# CONTROLLER-RK3562.net
KiCad netlist of a schematic drawn in Altium Designer
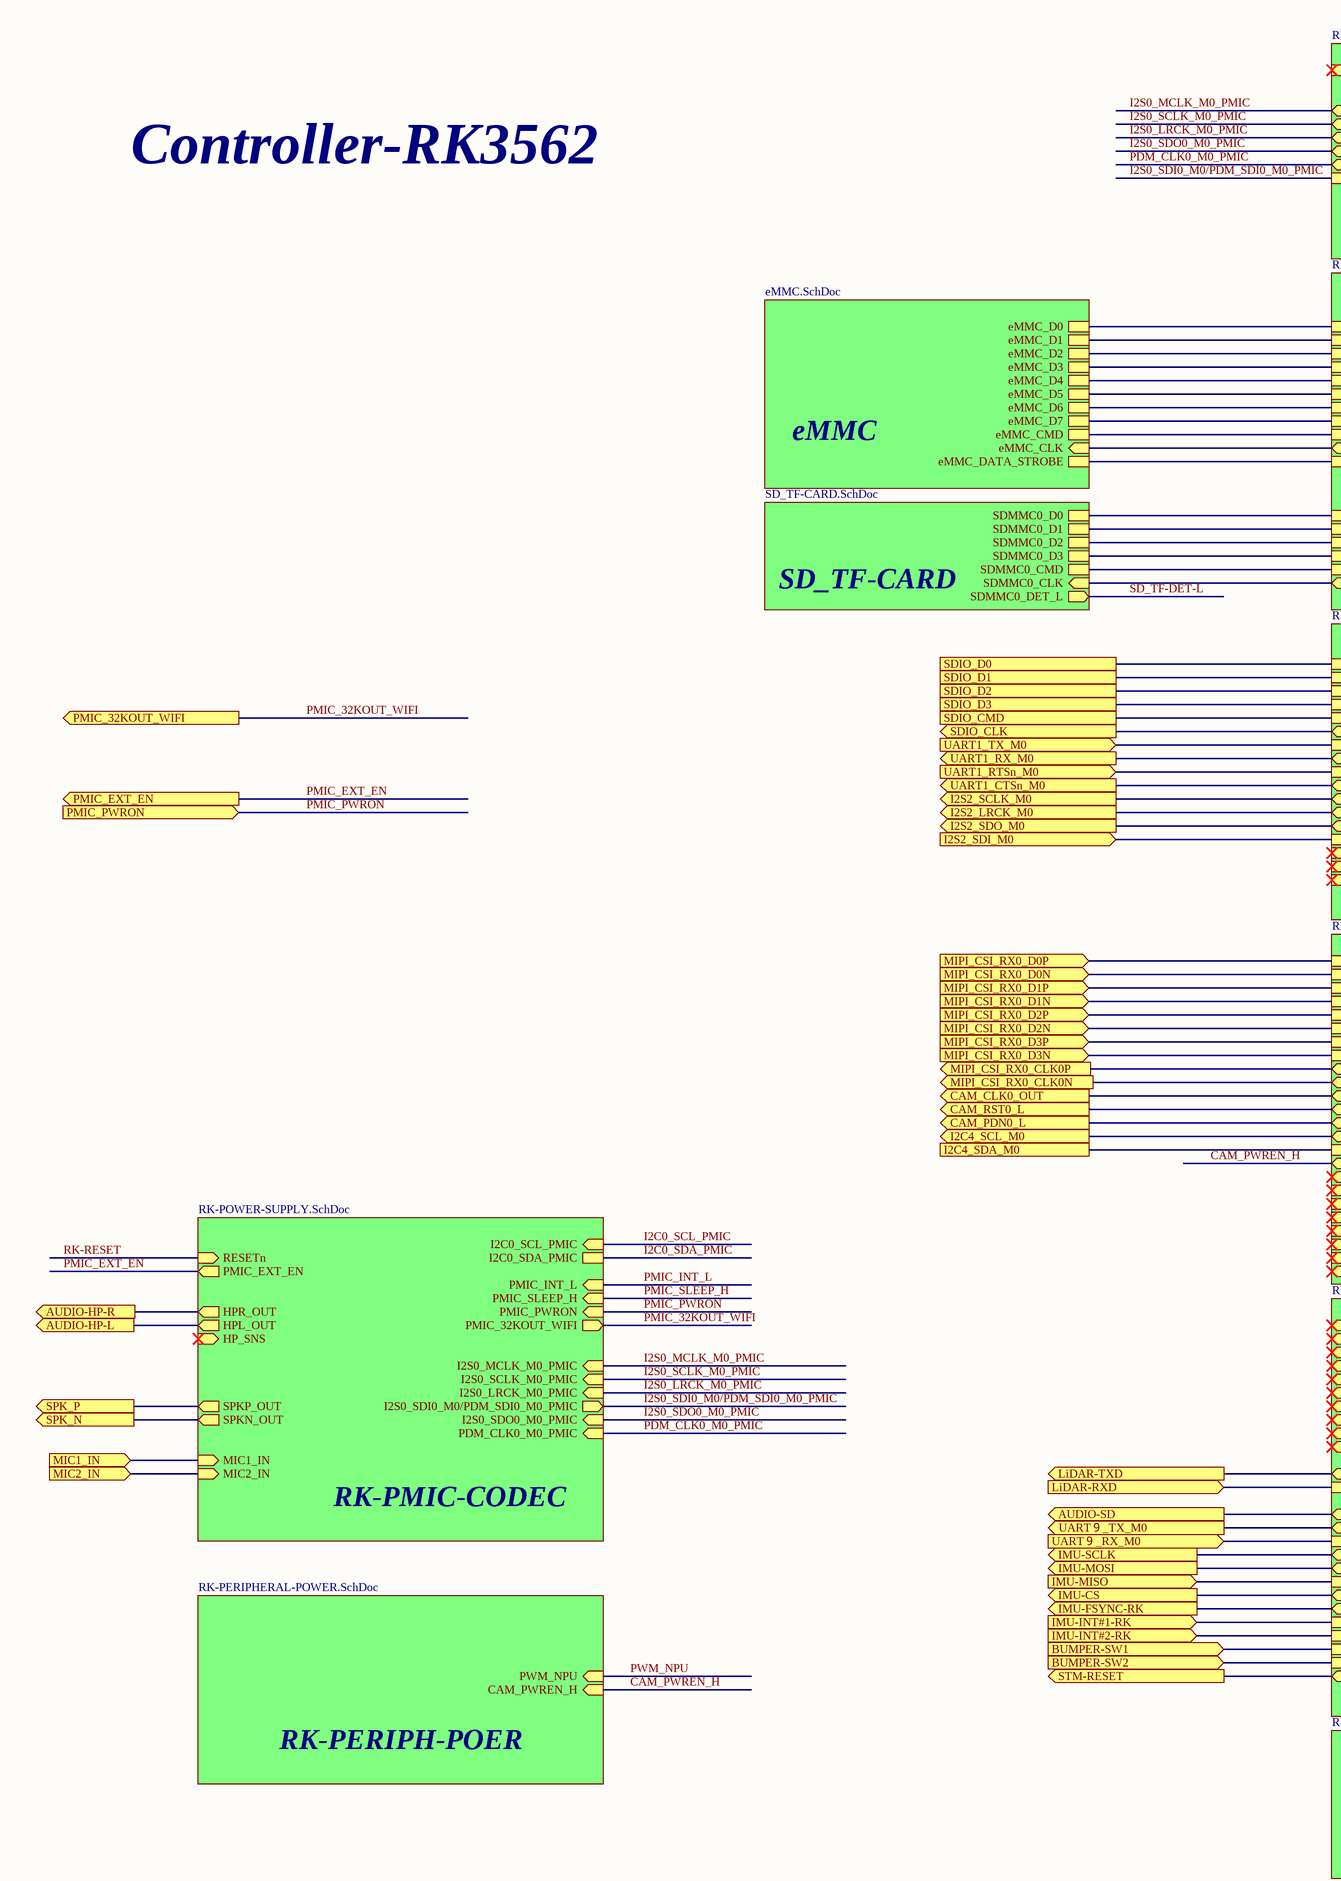
[diagram p0: CONTROLLER-RK3562.SchDoc, left]
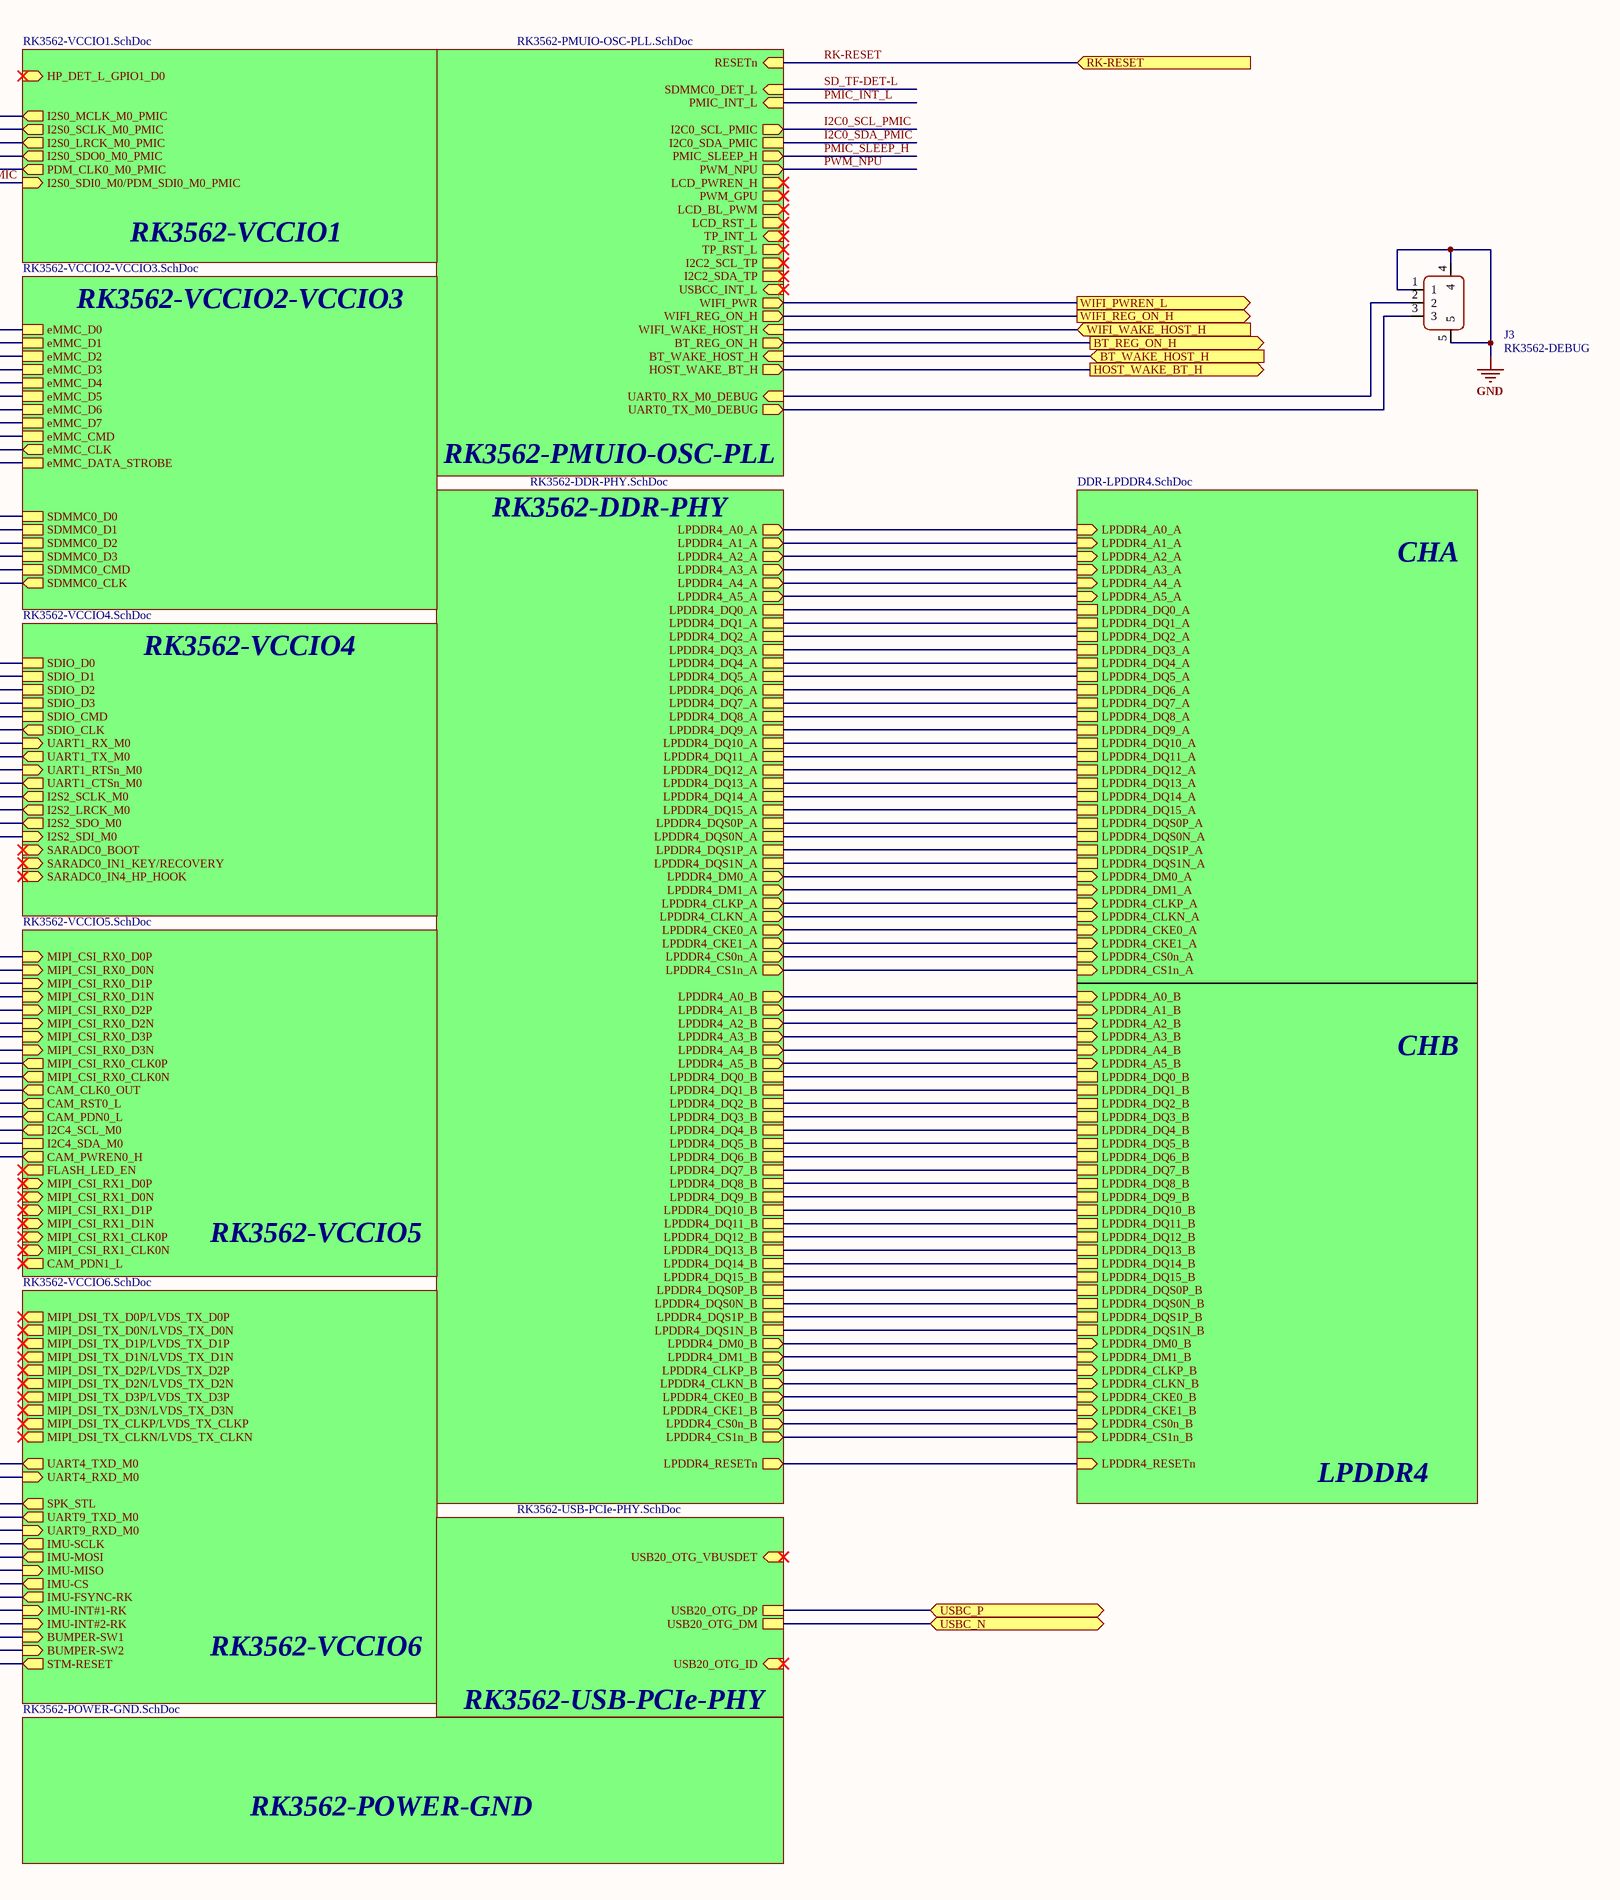
[diagram p1: CONTROLLER-RK3562.SchDoc, right]

(export (version "E")
  (design (tool "Eeschema 10.0.6"))
  (components
    (comp (ref "J3")
      (value "RK3562-DEBUG")
      (footprint "MHDR1X3")
      (libsource (lib "DesignLibrary") (part "HDRx3"))
    )
  )
  (nets
    (net (code "171") (name "/UART0_RX_M0_DEBUG") (class "Default")
      (node (ref "J3") (pin "2") (pinfunction "2_2") (pintype "passive"))
    )
    (net (code "172") (name "/UART0_TX_M0_DEBUG") (class "Default")
      (node (ref "J3") (pin "3") (pinfunction "3_3") (pintype "passive"))
    )
    (net (code "198") (name "GND") (class "Default")
      (node (ref "J3") (pin "1") (pinfunction "1_1") (pintype "passive"))
      (node (ref "J3") (pin "4") (pinfunction "4_4") (pintype "passive"))
      (node (ref "J3") (pin "5") (pinfunction "5_5") (pintype "passive"))
    )
  )
)
